# MAX9709_Mono_Bridge_AMP_1V2.net
KiCad netlist of a schematic drawn in EAGLE
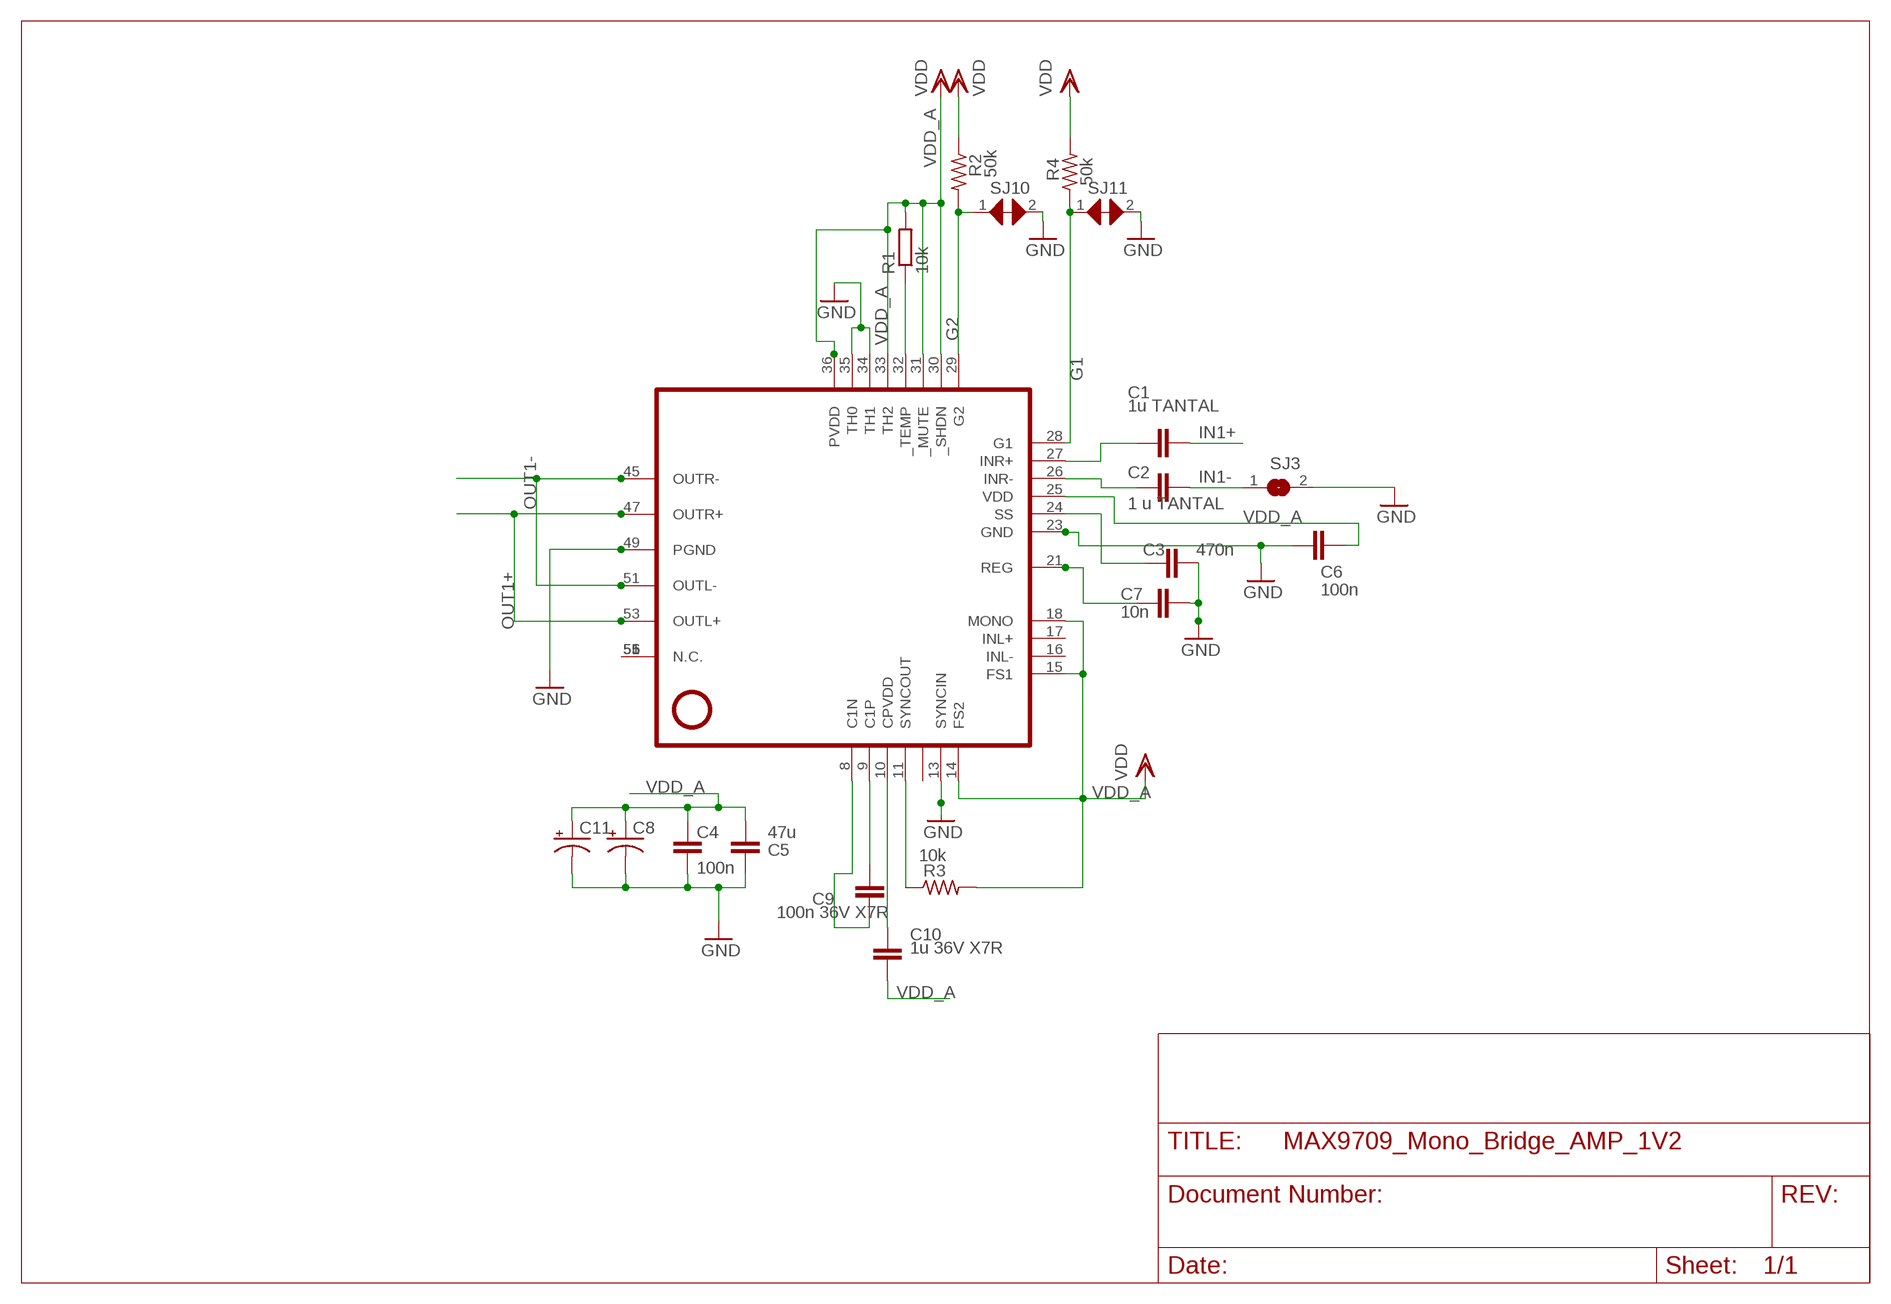
[diagram p0: schematic, sheet 1]

(export (version "E")
  (design (tool "Eeschema 10.0.6"))
  (components
    (comp (ref "C1")
      (value "1u TANTAL")
      (footprint "eagle-import:0805")
      (libsource (lib "eagle-import") (part "CAP-SMD0805"))
    )
    (comp (ref "C2")
      (value "1 u TANTAL")
      (footprint "eagle-import:0805")
      (libsource (lib "eagle-import") (part "CAP-SMD0805"))
    )
    (comp (ref "C3")
      (value "470n")
      (footprint "eagle-import:C0402K")
      (libsource (lib "eagle-import") (part "C-EUC0402K"))
    )
    (comp (ref "C4")
      (value "100n")
      (footprint "eagle-import:0603")
      (libsource (lib "eagle-import") (part "CAP-SMD0603"))
    )
    (comp (ref "C5")
      (value "47u")
      (footprint "eagle-import:0603")
      (libsource (lib "eagle-import") (part "CAP-SMD0603"))
    )
    (comp (ref "C6")
      (value "100n")
      (footprint "eagle-import:C0402K")
      (libsource (lib "eagle-import") (part "C-EUC0402K"))
    )
    (comp (ref "C7")
      (value "10n")
      (footprint "eagle-import:C0402K")
      (libsource (lib "eagle-import") (part "C-EUC0402K"))
    )
    (comp (ref "C8")
      (value "CPOL-USCT7343")
      (footprint "eagle-import:CT7343")
      (libsource (lib "eagle-import") (part "CPOL-USCT7343"))
    )
    (comp (ref "C9")
      (value "100n 36V X7R")
      (footprint "eagle-import:0805")
      (libsource (lib "eagle-import") (part "CAP-SMD0805"))
    )
    (comp (ref "C10")
      (value "1u 36V X7R")
      (footprint "eagle-import:0805")
      (libsource (lib "eagle-import") (part "CAP-SMD0805"))
    )
    (comp (ref "C11")
      (value "CPOL-USCT7343")
      (footprint "eagle-import:CT7343")
      (libsource (lib "eagle-import") (part "CPOL-USCT7343"))
    )
    (comp (ref "IC1")
      (value "MAX9709")
      (footprint "eagle-import:56-QFN")
      (libsource (lib "eagle-import") (part "MAX9709"))
    )
    (comp (ref "R1")
      (value "10k")
      (footprint "eagle-import:R0402")
      (libsource (lib "eagle-import") (part "R-EU_R0402"))
    )
    (comp (ref "R2")
      (value "50k")
      (footprint "eagle-import:R0402")
      (libsource (lib "eagle-import") (part "R-US_R0402"))
    )
    (comp (ref "R3")
      (value "10k")
      (footprint "eagle-import:R0402")
      (libsource (lib "eagle-import") (part "R-US_R0402"))
    )
    (comp (ref "R4")
      (value "50k")
      (footprint "eagle-import:R0402")
      (libsource (lib "eagle-import") (part "R-US_R0402"))
    )
    (comp (ref "SJ3")
      (value "JUMPER_SMD")
      (footprint "eagle-import:JUMPER_SMD_SJ")
      (libsource (lib "eagle-import") (part "JUMPER_SMD"))
    )
    (comp (ref "SJ10")
      (value "JUMPER_SMD_MICRO_SHORT")
      (footprint "eagle-import:JUMPER_SMD_MICRO_SHORT")
      (libsource (lib "eagle-import") (part "JUMPER_SMD_MICRO_SHORT"))
    )
    (comp (ref "SJ11")
      (value "JUMPER_SMD_MICRO_SHORT")
      (footprint "eagle-import:JUMPER_SMD_MICRO_SHORT")
      (libsource (lib "eagle-import") (part "JUMPER_SMD_MICRO_SHORT"))
    )
  )
  (nets
    (net (code "1") (name "/G1") (class "Default")
      (node (ref "IC1") (pin "28") (pinfunction "G1_28") (pintype "bidirectional"))
      (node (ref "R4") (pin "1") (pinfunction "1_1") (pintype "passive"))
      (node (ref "SJ11") (pin "1") (pinfunction "1_1") (pintype "passive"))
    )
    (net (code "2") (name "/G2") (class "Default")
      (node (ref "IC1") (pin "29") (pinfunction "G2_29") (pintype "bidirectional"))
      (node (ref "R2") (pin "2") (pinfunction "2_2") (pintype "passive"))
      (node (ref "SJ10") (pin "1") (pinfunction "1_1") (pintype "passive"))
    )
    (net (code "3") (name "/IN1+") (class "Default")
      (node (ref "C1") (pin "P$1") (pinfunction "1_P$1") (pintype "passive"))
    )
    (net (code "4") (name "/IN1-") (class "Default")
      (node (ref "C2") (pin "P$1") (pinfunction "1_P$1") (pintype "passive"))
      (node (ref "SJ3") (pin "1") (pinfunction "1_1") (pintype "passive"))
    )
    (net (code "5") (name "/OUT1+") (class "Default")
      (node (ref "IC1") (pin "47") (pinfunction "OUTR+_47") (pintype "power_in"))
      (node (ref "IC1") (pin "48") (pinfunction "OUTR+2_48") (pintype "power_in"))
      (node (ref "IC1") (pin "53") (pinfunction "OUTL+_53") (pintype "power_in"))
      (node (ref "IC1") (pin "54") (pinfunction "OUTL+2_54") (pintype "power_in"))
    )
    (net (code "6") (name "/OUT1-") (class "Default")
      (node (ref "IC1") (pin "45") (pinfunction "OUTR-_45") (pintype "power_in"))
      (node (ref "IC1") (pin "46") (pinfunction "OUTR-2_46") (pintype "power_in"))
      (node (ref "IC1") (pin "51") (pinfunction "OUTL-_51") (pintype "power_in"))
      (node (ref "IC1") (pin "52") (pinfunction "OUTL-2_52") (pintype "power_in"))
    )
    (net (code "7") (name "GND") (class "Default")
      (node (ref "C11") (pin "-") (pinfunction "-_-") (pintype "passive"))
      (node (ref "C3") (pin "2") (pinfunction "2_2") (pintype "passive"))
      (node (ref "C4") (pin "2") (pinfunction "2_2") (pintype "passive"))
      (node (ref "C5") (pin "2") (pinfunction "2_2") (pintype "passive"))
      (node (ref "C6") (pin "1") (pinfunction "1_1") (pintype "passive"))
      (node (ref "C7") (pin "2") (pinfunction "2_2") (pintype "passive"))
      (node (ref "C8") (pin "-") (pinfunction "-_-") (pintype "passive"))
      (node (ref "IC1") (pin "13") (pinfunction "SYNCIN_13") (pintype "bidirectional"))
      (node (ref "IC1") (pin "2") (pinfunction "PGND$2_2") (pintype "power_in"))
      (node (ref "IC1") (pin "22") (pinfunction "GND2_22") (pintype "power_in"))
      (node (ref "IC1") (pin "23") (pinfunction "GND_23") (pintype "power_in"))
      (node (ref "IC1") (pin "3") (pinfunction "PGND$3_3") (pintype "power_in"))
      (node (ref "IC1") (pin "34") (pinfunction "TH1_34") (pintype "bidirectional"))
      (node (ref "IC1") (pin "35") (pinfunction "TH0_35") (pintype "bidirectional"))
      (node (ref "IC1") (pin "39") (pinfunction "PGND$39_39") (pintype "power_in"))
      (node (ref "IC1") (pin "4") (pinfunction "PGND$4_4") (pintype "power_in"))
      (node (ref "IC1") (pin "40") (pinfunction "PGND$40_40") (pintype "power_in"))
      (node (ref "IC1") (pin "41") (pinfunction "PGND$41_41") (pintype "power_in"))
      (node (ref "IC1") (pin "49") (pinfunction "PGND_49") (pintype "power_in"))
      (node (ref "IC1") (pin "50") (pinfunction "PGND$8_50") (pintype "power_in"))
      (node (ref "IC1") (pin "P$1") (pinfunction "GND1_P$1") (pintype "power_in"))
      (node (ref "IC1") (pin "P$10") (pinfunction "GND11_P$10") (pintype "power_in"))
      (node (ref "IC1") (pin "P$11") (pinfunction "GND12_P$11") (pintype "power_in"))
      (node (ref "IC1") (pin "P$12") (pinfunction "GND13_P$12") (pintype "power_in"))
      (node (ref "IC1") (pin "P$13") (pinfunction "GND14_P$13") (pintype "power_in"))
      (node (ref "IC1") (pin "P$14") (pinfunction "GND15_P$14") (pintype "power_in"))
      (node (ref "IC1") (pin "P$15") (pinfunction "GND16_P$15") (pintype "power_in"))
      (node (ref "IC1") (pin "P$16") (pinfunction "GND17_P$16") (pintype "power_in"))
      (node (ref "IC1") (pin "P$17") (pinfunction "GND18_P$17") (pintype "power_in"))
      (node (ref "IC1") (pin "P$18") (pinfunction "GND19_P$18") (pintype "power_in"))
      (node (ref "IC1") (pin "P$19") (pinfunction "GND20_P$19") (pintype "power_in"))
      (node (ref "IC1") (pin "P$2") (pinfunction "GND3_P$2") (pintype "power_in"))
      (node (ref "IC1") (pin "P$20") (pinfunction "GND21_P$20") (pintype "power_in"))
      (node (ref "IC1") (pin "P$21") (pinfunction "GND22_P$21") (pintype "power_in"))
      (node (ref "IC1") (pin "P$22") (pinfunction "GND23_P$22") (pintype "power_in"))
      (node (ref "IC1") (pin "P$23") (pinfunction "GND24_P$23") (pintype "power_in"))
      (node (ref "IC1") (pin "P$24") (pinfunction "GND25_P$24") (pintype "power_in"))
      (node (ref "IC1") (pin "P$25") (pinfunction "GND26_P$25") (pintype "power_in"))
      (node (ref "IC1") (pin "P$3") (pinfunction "GND4_P$3") (pintype "power_in"))
      (node (ref "IC1") (pin "P$4") (pinfunction "GND5_P$4") (pintype "power_in"))
      (node (ref "IC1") (pin "P$5") (pinfunction "GND6_P$5") (pintype "power_in"))
      (node (ref "IC1") (pin "P$6") (pinfunction "GND7_P$6") (pintype "power_in"))
      (node (ref "IC1") (pin "P$7") (pinfunction "GND8_P$7") (pintype "power_in"))
      (node (ref "IC1") (pin "P$8") (pinfunction "GND9_P$8") (pintype "power_in"))
      (node (ref "IC1") (pin "P$9") (pinfunction "GND10_P$9") (pintype "power_in"))
      (node (ref "SJ10") (pin "2") (pinfunction "2_2") (pintype "passive"))
      (node (ref "SJ11") (pin "2") (pinfunction "2_2") (pintype "passive"))
      (node (ref "SJ3") (pin "2") (pinfunction "2_2") (pintype "passive"))
    )
    (net (code "8") (name "Net-(C1-2)") (class "Default")
      (node (ref "C1") (pin "P$2") (pinfunction "2_P$2") (pintype "passive"))
      (node (ref "IC1") (pin "27") (pinfunction "INR+_27") (pintype "bidirectional"))
    )
    (net (code "9") (name "Net-(C2-2)") (class "Default")
      (node (ref "C2") (pin "P$2") (pinfunction "2_P$2") (pintype "passive"))
      (node (ref "IC1") (pin "26") (pinfunction "INR-_26") (pintype "bidirectional"))
    )
    (net (code "10") (name "Net-(C9-1)") (class "Default")
      (node (ref "C9") (pin "P$1") (pinfunction "1_P$1") (pintype "passive"))
      (node (ref "IC1") (pin "8") (pinfunction "C1N_8") (pintype "bidirectional"))
    )
    (net (code "11") (name "Net-(C9-2)") (class "Default")
      (node (ref "C9") (pin "P$2") (pinfunction "2_P$2") (pintype "passive"))
      (node (ref "IC1") (pin "9") (pinfunction "C1P_9") (pintype "bidirectional"))
    )
    (net (code "12") (name "Net-(C10-2)") (class "Default")
      (node (ref "C10") (pin "P$2") (pinfunction "2_P$2") (pintype "passive"))
      (node (ref "IC1") (pin "10") (pinfunction "CPVDD_10") (pintype "bidirectional"))
    )
    (net (code "13") (name "Net-(IC1-REG)") (class "Default")
      (node (ref "C7") (pin "1") (pinfunction "1_1") (pintype "passive"))
      (node (ref "IC1") (pin "19") (pinfunction "REG3_19") (pintype "power_in"))
      (node (ref "IC1") (pin "20") (pinfunction "REG2_20") (pintype "power_in"))
      (node (ref "IC1") (pin "21") (pinfunction "REG_21") (pintype "power_in"))
    )
    (net (code "14") (name "Net-(IC1-SS)") (class "Default")
      (node (ref "C3") (pin "1") (pinfunction "1_1") (pintype "passive"))
      (node (ref "IC1") (pin "24") (pinfunction "SS_24") (pintype "bidirectional"))
    )
    (net (code "15") (name "Net-(IC1-SYNCOUT)") (class "Default")
      (node (ref "IC1") (pin "11") (pinfunction "SYNCOUT_11") (pintype "bidirectional"))
      (node (ref "R3") (pin "1") (pinfunction "1_1") (pintype "passive"))
    )
    (net (code "16") (name "Net-(IC1-_TEMP)") (class "Default")
      (node (ref "IC1") (pin "32") (pinfunction "_TEMP_32") (pintype "bidirectional"))
      (node (ref "R1") (pin "1") (pinfunction "1_1") (pintype "passive"))
    )
    (net (code "17") (name "VDD") (class "Default")
      (node (ref "C10") (pin "P$1") (pinfunction "1_P$1") (pintype "passive"))
      (node (ref "C11") (pin "+") (pinfunction "+_+") (pintype "passive"))
      (node (ref "C4") (pin "1") (pinfunction "1_1") (pintype "passive"))
      (node (ref "C5") (pin "1") (pinfunction "1_1") (pintype "passive"))
      (node (ref "C6") (pin "2") (pinfunction "2_2") (pintype "passive"))
      (node (ref "C8") (pin "+") (pinfunction "+_+") (pintype "passive"))
      (node (ref "IC1") (pin "14") (pinfunction "FS2_14") (pintype "bidirectional"))
      (node (ref "IC1") (pin "15") (pinfunction "FS1_15") (pintype "bidirectional"))
      (node (ref "IC1") (pin "18") (pinfunction "MONO_18") (pintype "bidirectional"))
      (node (ref "IC1") (pin "25") (pinfunction "VDD_25") (pintype "bidirectional"))
      (node (ref "IC1") (pin "30") (pinfunction "_SHDN_30") (pintype "bidirectional"))
      (node (ref "IC1") (pin "31") (pinfunction "_MUTE_31") (pintype "bidirectional"))
      (node (ref "IC1") (pin "33") (pinfunction "TH2_33") (pintype "bidirectional"))
      (node (ref "IC1") (pin "36") (pinfunction "PVDD_36") (pintype "power_in"))
      (node (ref "IC1") (pin "37") (pinfunction "PVDD$37_37") (pintype "power_in"))
      (node (ref "IC1") (pin "38") (pinfunction "PVDD$38_38") (pintype "power_in"))
      (node (ref "IC1") (pin "5") (pinfunction "PVDD$5_5") (pintype "power_in"))
      (node (ref "IC1") (pin "6") (pinfunction "PVDD$6_6") (pintype "power_in"))
      (node (ref "IC1") (pin "7") (pinfunction "PVDD$7_7") (pintype "power_in"))
      (node (ref "R1") (pin "2") (pinfunction "2_2") (pintype "passive"))
      (node (ref "R2") (pin "1") (pinfunction "1_1") (pintype "passive"))
      (node (ref "R3") (pin "2") (pinfunction "2_2") (pintype "passive"))
      (node (ref "R4") (pin "2") (pinfunction "2_2") (pintype "passive"))
    )
    (net (code "18") (name "unconnected-(IC1-INL+-Pad17)") (class "Default")
      (node (ref "IC1") (pin "17") (pinfunction "INL+_17") (pintype "bidirectional"))
    )
    (net (code "19") (name "unconnected-(IC1-INL--Pad16)") (class "Default")
      (node (ref "IC1") (pin "16") (pinfunction "INL-_16") (pintype "bidirectional"))
    )
    (net (code "20") (name "unconnected-(IC1-N.C.$12-Pad12)") (class "Default")
      (node (ref "IC1") (pin "12") (pinfunction "N.C.$12_12") (pintype "no_connect"))
    )
    (net (code "21") (name "unconnected-(IC1-N.C.$42-Pad42)") (class "Default")
      (node (ref "IC1") (pin "42") (pinfunction "N.C.$42_42") (pintype "no_connect"))
    )
    (net (code "22") (name "unconnected-(IC1-N.C.$43-Pad43)") (class "Default")
      (node (ref "IC1") (pin "43") (pinfunction "N.C.$43_43") (pintype "no_connect"))
    )
    (net (code "23") (name "unconnected-(IC1-N.C.$44-Pad44)") (class "Default")
      (node (ref "IC1") (pin "44") (pinfunction "N.C.$44_44") (pintype "no_connect"))
    )
    (net (code "24") (name "unconnected-(IC1-N.C.$55-Pad55)") (class "Default")
      (node (ref "IC1") (pin "55") (pinfunction "N.C.$55_55") (pintype "no_connect"))
    )
    (net (code "25") (name "unconnected-(IC1-N.C.$56-Pad56)") (class "Default")
      (node (ref "IC1") (pin "56") (pinfunction "N.C.$56_56") (pintype "no_connect"))
    )
    (net (code "26") (name "unconnected-(IC1-N.C.-Pad1)") (class "Default")
      (node (ref "IC1") (pin "1") (pinfunction "N.C._1") (pintype "no_connect"))
    )
  )
)
